# monitoring.net
KiCad netlist of a schematic drawn in EAGLE
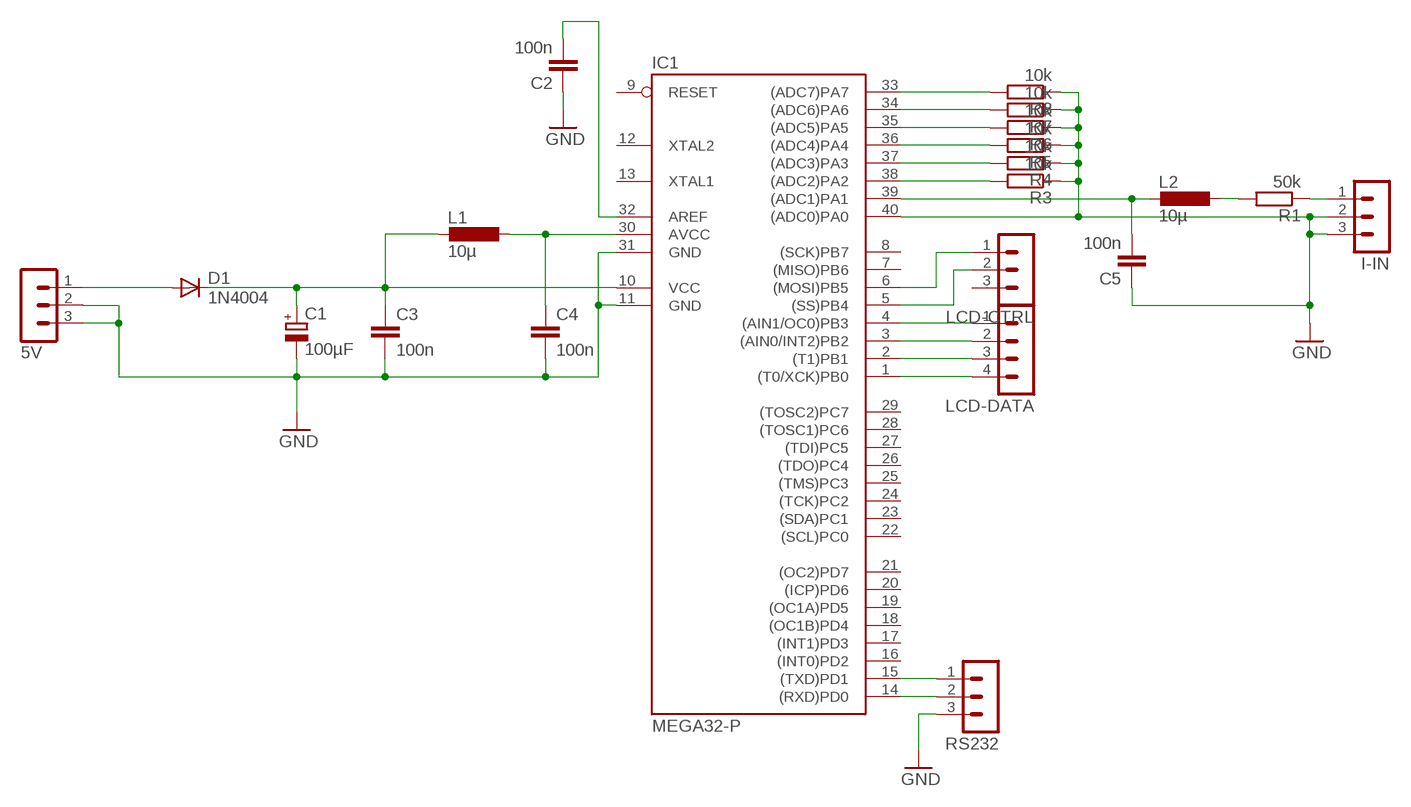
[diagram p0: schematic, sheet 1]

(export (version "E")
  (design (tool "Eeschema 10.0.6"))
  (components
    (comp (ref "5V")
      (value "MA03-1")
      (footprint "eagle-import:MA03-1")
      (libsource (lib "eagle-import") (part "MA03-1"))
    )
    (comp (ref "C1")
      (value "100µF")
      (footprint "eagle-import:E5-10,5")
      (libsource (lib "eagle-import") (part "CPOL-EUE5-10.5"))
    )
    (comp (ref "C2")
      (value "100n")
      (footprint "eagle-import:C050-035X075")
      (libsource (lib "eagle-import") (part "C-EU050-035X075"))
    )
    (comp (ref "C3")
      (value "100n")
      (footprint "eagle-import:C050-035X075")
      (libsource (lib "eagle-import") (part "C-EU050-035X075"))
    )
    (comp (ref "C4")
      (value "100n")
      (footprint "eagle-import:C050-035X075")
      (libsource (lib "eagle-import") (part "C-EU050-035X075"))
    )
    (comp (ref "C5")
      (value "100n")
      (footprint "eagle-import:C050-035X075")
      (libsource (lib "eagle-import") (part "C-EU050-035X075"))
    )
    (comp (ref "D1")
      (value "1N4004")
      (footprint "eagle-import:DO41-10")
      (libsource (lib "eagle-import") (part "1N4004"))
    )
    (comp (ref "I-IN")
      (value "MA03-1")
      (footprint "eagle-import:MA03-1")
      (libsource (lib "eagle-import") (part "MA03-1"))
    )
    (comp (ref "IC1")
      (value "MEGA32-P")
      (footprint "eagle-import:DIL40")
      (fields (field (name "MPN") "ATMEGA32-16PU"))
      (libsource (lib "eagle-import") (part "MEGA32-P"))
    )
    (comp (ref "L1")
      (value "10µ")
      (footprint "eagle-import:0204V")
      (libsource (lib "eagle-import") (part "L-EU0204V"))
    )
    (comp (ref "L2")
      (value "10µ")
      (footprint "eagle-import:0207_10")
      (libsource (lib "eagle-import") (part "L-EU0207/10"))
    )
    (comp (ref "LCD-CTRL")
      (value "MA03-1")
      (footprint "eagle-import:MA03-1")
      (libsource (lib "eagle-import") (part "MA03-1"))
    )
    (comp (ref "LCD-DATA")
      (value "MA04-1")
      (footprint "eagle-import:MA04-1")
      (libsource (lib "eagle-import") (part "MA04-1"))
    )
    (comp (ref "R1")
      (value "50k")
      (footprint "eagle-import:0204V")
      (libsource (lib "eagle-import") (part "R-EU_0204/2V"))
    )
    (comp (ref "R3")
      (value "10k")
      (footprint "eagle-import:0204V")
      (libsource (lib "eagle-import") (part "R-EU_0204/2V"))
    )
    (comp (ref "R4")
      (value "10k")
      (footprint "eagle-import:0204V")
      (libsource (lib "eagle-import") (part "R-EU_0204/2V"))
    )
    (comp (ref "R5")
      (value "10k")
      (footprint "eagle-import:0204V")
      (libsource (lib "eagle-import") (part "R-EU_0204/2V"))
    )
    (comp (ref "R6")
      (value "10k")
      (footprint "eagle-import:0204V")
      (libsource (lib "eagle-import") (part "R-EU_0204/2V"))
    )
    (comp (ref "R7")
      (value "10k")
      (footprint "eagle-import:0204V")
      (libsource (lib "eagle-import") (part "R-EU_0204/2V"))
    )
    (comp (ref "R8")
      (value "10k")
      (footprint "eagle-import:0204V")
      (libsource (lib "eagle-import") (part "R-EU_0204/2V"))
    )
    (comp (ref "RS232")
      (value "MA03-1")
      (footprint "eagle-import:MA03-1")
      (libsource (lib "eagle-import") (part "MA03-1"))
    )
  )
  (nets
    (net (code "1") (name "GND") (class "Default")
      (node (ref "5V") (pin "2") (pinfunction "2_2") (pintype "passive"))
      (node (ref "5V") (pin "3") (pinfunction "3_3") (pintype "passive"))
      (node (ref "C1") (pin "-") (pinfunction "-_-") (pintype "passive"))
      (node (ref "C2") (pin "1") (pinfunction "1_1") (pintype "passive"))
      (node (ref "C3") (pin "2") (pinfunction "2_2") (pintype "passive"))
      (node (ref "C4") (pin "2") (pinfunction "2_2") (pintype "passive"))
      (node (ref "C5") (pin "1") (pinfunction "1_1") (pintype "passive"))
      (node (ref "I-IN") (pin "2") (pinfunction "2_2") (pintype "passive"))
      (node (ref "I-IN") (pin "3") (pinfunction "3_3") (pintype "passive"))
      (node (ref "IC1") (pin "11") (pinfunction "GND_11") (pintype "power_in"))
      (node (ref "IC1") (pin "31") (pinfunction "GND_31") (pintype "power_in"))
      (node (ref "IC1") (pin "40") (pinfunction "(ADC0)PA0_40") (pintype "bidirectional"))
      (node (ref "R3") (pin "1") (pinfunction "1_1") (pintype "passive"))
      (node (ref "R4") (pin "1") (pinfunction "1_1") (pintype "passive"))
      (node (ref "R5") (pin "1") (pinfunction "1_1") (pintype "passive"))
      (node (ref "R6") (pin "1") (pinfunction "1_1") (pintype "passive"))
      (node (ref "R7") (pin "1") (pinfunction "1_1") (pintype "passive"))
      (node (ref "R8") (pin "1") (pinfunction "1_1") (pintype "passive"))
      (node (ref "RS232") (pin "3") (pinfunction "3_3") (pintype "passive"))
    )
    (net (code "2") (name "Net-(5V-Pad1)") (class "Default")
      (node (ref "5V") (pin "1") (pinfunction "1_1") (pintype "passive"))
      (node (ref "D1") (pin "A") (pinfunction "A_A") (pintype "passive"))
    )
    (net (code "3") (name "Net-(I-IN-Pad1)") (class "Default")
      (node (ref "I-IN") (pin "1") (pinfunction "1_1") (pintype "passive"))
      (node (ref "R1") (pin "1") (pinfunction "1_1") (pintype "passive"))
    )
    (net (code "4") (name "Net-(IC1-(ADC1)PA1)") (class "Default")
      (node (ref "C5") (pin "2") (pinfunction "2_2") (pintype "passive"))
      (node (ref "IC1") (pin "39") (pinfunction "(ADC1)PA1_39") (pintype "bidirectional"))
      (node (ref "L2") (pin "2") (pinfunction "2_2") (pintype "passive"))
    )
    (net (code "5") (name "Net-(IC1-(ADC2)PA2)") (class "Default")
      (node (ref "IC1") (pin "38") (pinfunction "(ADC2)PA2_38") (pintype "bidirectional"))
      (node (ref "R3") (pin "2") (pinfunction "2_2") (pintype "passive"))
    )
    (net (code "6") (name "Net-(IC1-(ADC3)PA3)") (class "Default")
      (node (ref "IC1") (pin "37") (pinfunction "(ADC3)PA3_37") (pintype "bidirectional"))
      (node (ref "R4") (pin "2") (pinfunction "2_2") (pintype "passive"))
    )
    (net (code "7") (name "Net-(IC1-(ADC4)PA4)") (class "Default")
      (node (ref "IC1") (pin "36") (pinfunction "(ADC4)PA4_36") (pintype "bidirectional"))
      (node (ref "R5") (pin "2") (pinfunction "2_2") (pintype "passive"))
    )
    (net (code "8") (name "Net-(IC1-(ADC5)PA5)") (class "Default")
      (node (ref "IC1") (pin "35") (pinfunction "(ADC5)PA5_35") (pintype "bidirectional"))
      (node (ref "R6") (pin "2") (pinfunction "2_2") (pintype "passive"))
    )
    (net (code "9") (name "Net-(IC1-(ADC6)PA6)") (class "Default")
      (node (ref "IC1") (pin "34") (pinfunction "(ADC6)PA6_34") (pintype "bidirectional"))
      (node (ref "R7") (pin "2") (pinfunction "2_2") (pintype "passive"))
    )
    (net (code "10") (name "Net-(IC1-(ADC7)PA7)") (class "Default")
      (node (ref "IC1") (pin "33") (pinfunction "(ADC7)PA7_33") (pintype "bidirectional"))
      (node (ref "R8") (pin "2") (pinfunction "2_2") (pintype "passive"))
    )
    (net (code "11") (name "Net-(IC1-(AIN0{slash}INT2)PB2)") (class "Default")
      (node (ref "IC1") (pin "3") (pinfunction "(AIN0/INT2)PB2_3") (pintype "bidirectional"))
      (node (ref "LCD-DATA") (pin "2") (pinfunction "2_2") (pintype "passive"))
    )
    (net (code "12") (name "Net-(IC1-(AIN1{slash}OC0)PB3)") (class "Default")
      (node (ref "IC1") (pin "4") (pinfunction "(AIN1/OC0)PB3_4") (pintype "bidirectional"))
      (node (ref "LCD-DATA") (pin "1") (pinfunction "1_1") (pintype "passive"))
    )
    (net (code "13") (name "Net-(IC1-(MOSI)PB5)") (class "Default")
      (node (ref "IC1") (pin "6") (pinfunction "(MOSI)PB5_6") (pintype "bidirectional"))
      (node (ref "LCD-CTRL") (pin "1") (pinfunction "1_1") (pintype "passive"))
    )
    (net (code "14") (name "Net-(IC1-(RXD)PD0)") (class "Default")
      (node (ref "IC1") (pin "14") (pinfunction "(RXD)PD0_14") (pintype "bidirectional"))
      (node (ref "RS232") (pin "2") (pinfunction "2_2") (pintype "passive"))
    )
    (net (code "15") (name "Net-(IC1-(SS)PB4)") (class "Default")
      (node (ref "IC1") (pin "5") (pinfunction "(SS)PB4_5") (pintype "bidirectional"))
      (node (ref "LCD-CTRL") (pin "2") (pinfunction "2_2") (pintype "passive"))
    )
    (net (code "16") (name "Net-(IC1-(T0{slash}XCK)PB0)") (class "Default")
      (node (ref "IC1") (pin "1") (pinfunction "(T0/XCK)PB0_1") (pintype "bidirectional"))
      (node (ref "LCD-DATA") (pin "4") (pinfunction "4_4") (pintype "passive"))
    )
    (net (code "17") (name "Net-(IC1-(T1)PB1)") (class "Default")
      (node (ref "IC1") (pin "2") (pinfunction "(T1)PB1_2") (pintype "bidirectional"))
      (node (ref "LCD-DATA") (pin "3") (pinfunction "3_3") (pintype "passive"))
    )
    (net (code "18") (name "Net-(IC1-(TXD)PD1)") (class "Default")
      (node (ref "IC1") (pin "15") (pinfunction "(TXD)PD1_15") (pintype "bidirectional"))
      (node (ref "RS232") (pin "1") (pinfunction "1_1") (pintype "passive"))
    )
    (net (code "19") (name "Net-(IC1-AREF)") (class "Default")
      (node (ref "C2") (pin "2") (pinfunction "2_2") (pintype "passive"))
      (node (ref "IC1") (pin "32") (pinfunction "AREF_32") (pintype "passive"))
    )
    (net (code "20") (name "Net-(IC1-AVCC)") (class "Default")
      (node (ref "C4") (pin "1") (pinfunction "1_1") (pintype "passive"))
      (node (ref "IC1") (pin "30") (pinfunction "AVCC_30") (pintype "power_in"))
      (node (ref "L1") (pin "1") (pinfunction "1_1") (pintype "passive"))
    )
    (net (code "21") (name "Net-(IC1-VCC)") (class "Default")
      (node (ref "C1") (pin "+") (pinfunction "+_+") (pintype "passive"))
      (node (ref "C3") (pin "1") (pinfunction "1_1") (pintype "passive"))
      (node (ref "D1") (pin "C") (pinfunction "C_C") (pintype "passive"))
      (node (ref "IC1") (pin "10") (pinfunction "VCC_10") (pintype "power_in"))
      (node (ref "L1") (pin "2") (pinfunction "2_2") (pintype "passive"))
    )
    (net (code "22") (name "Net-(L2-Pad1)") (class "Default")
      (node (ref "L2") (pin "1") (pinfunction "1_1") (pintype "passive"))
      (node (ref "R1") (pin "2") (pinfunction "2_2") (pintype "passive"))
    )
    (net (code "23") (name "unconnected-(IC1-(ICP)PD6-Pad20)") (class "Default")
      (node (ref "IC1") (pin "20") (pinfunction "(ICP)PD6_20") (pintype "bidirectional"))
    )
    (net (code "24") (name "unconnected-(IC1-(INT0)PD2-Pad16)") (class "Default")
      (node (ref "IC1") (pin "16") (pinfunction "(INT0)PD2_16") (pintype "bidirectional"))
    )
    (net (code "25") (name "unconnected-(IC1-(INT1)PD3-Pad17)") (class "Default")
      (node (ref "IC1") (pin "17") (pinfunction "(INT1)PD3_17") (pintype "bidirectional"))
    )
    (net (code "26") (name "unconnected-(IC1-(MISO)PB6-Pad7)") (class "Default")
      (node (ref "IC1") (pin "7") (pinfunction "(MISO)PB6_7") (pintype "bidirectional"))
    )
    (net (code "27") (name "unconnected-(IC1-(OC1A)PD5-Pad19)") (class "Default")
      (node (ref "IC1") (pin "19") (pinfunction "(OC1A)PD5_19") (pintype "bidirectional"))
    )
    (net (code "28") (name "unconnected-(IC1-(OC1B)PD4-Pad18)") (class "Default")
      (node (ref "IC1") (pin "18") (pinfunction "(OC1B)PD4_18") (pintype "bidirectional"))
    )
    (net (code "29") (name "unconnected-(IC1-(OC2)PD7-Pad21)") (class "Default")
      (node (ref "IC1") (pin "21") (pinfunction "(OC2)PD7_21") (pintype "bidirectional"))
    )
    (net (code "30") (name "unconnected-(IC1-(SCK)PB7-Pad8)") (class "Default")
      (node (ref "IC1") (pin "8") (pinfunction "(SCK)PB7_8") (pintype "bidirectional"))
    )
    (net (code "31") (name "unconnected-(IC1-(SCL)PC0-Pad22)") (class "Default")
      (node (ref "IC1") (pin "22") (pinfunction "(SCL)PC0_22") (pintype "bidirectional"))
    )
    (net (code "32") (name "unconnected-(IC1-(SDA)PC1-Pad23)") (class "Default")
      (node (ref "IC1") (pin "23") (pinfunction "(SDA)PC1_23") (pintype "bidirectional"))
    )
    (net (code "33") (name "unconnected-(IC1-(TCK)PC2-Pad24)") (class "Default")
      (node (ref "IC1") (pin "24") (pinfunction "(TCK)PC2_24") (pintype "bidirectional"))
    )
    (net (code "34") (name "unconnected-(IC1-(TDI)PC5-Pad27)") (class "Default")
      (node (ref "IC1") (pin "27") (pinfunction "(TDI)PC5_27") (pintype "bidirectional"))
    )
    (net (code "35") (name "unconnected-(IC1-(TDO)PC4-Pad26)") (class "Default")
      (node (ref "IC1") (pin "26") (pinfunction "(TDO)PC4_26") (pintype "bidirectional"))
    )
    (net (code "36") (name "unconnected-(IC1-(TMS)PC3-Pad25)") (class "Default")
      (node (ref "IC1") (pin "25") (pinfunction "(TMS)PC3_25") (pintype "bidirectional"))
    )
    (net (code "37") (name "unconnected-(IC1-(TOSC1)PC6-Pad28)") (class "Default")
      (node (ref "IC1") (pin "28") (pinfunction "(TOSC1)PC6_28") (pintype "bidirectional"))
    )
    (net (code "38") (name "unconnected-(IC1-(TOSC2)PC7-Pad29)") (class "Default")
      (node (ref "IC1") (pin "29") (pinfunction "(TOSC2)PC7_29") (pintype "bidirectional"))
    )
    (net (code "39") (name "unconnected-(IC1-RESET-Pad9)") (class "Default")
      (node (ref "IC1") (pin "9") (pinfunction "RESET_9") (pintype "input"))
    )
    (net (code "40") (name "unconnected-(IC1-XTAL1-Pad13)") (class "Default")
      (node (ref "IC1") (pin "13") (pinfunction "XTAL1_13") (pintype "bidirectional"))
    )
    (net (code "41") (name "unconnected-(IC1-XTAL2-Pad12)") (class "Default")
      (node (ref "IC1") (pin "12") (pinfunction "XTAL2_12") (pintype "bidirectional"))
    )
    (net (code "42") (name "unconnected-(LCD-CTRL-Pad3)") (class "Default")
      (node (ref "LCD-CTRL") (pin "3") (pinfunction "3_3") (pintype "passive"))
    )
  )
)
